# FIT_TCM_ADCLK854.net
KiCad netlist of a schematic drawn in Altium Designer
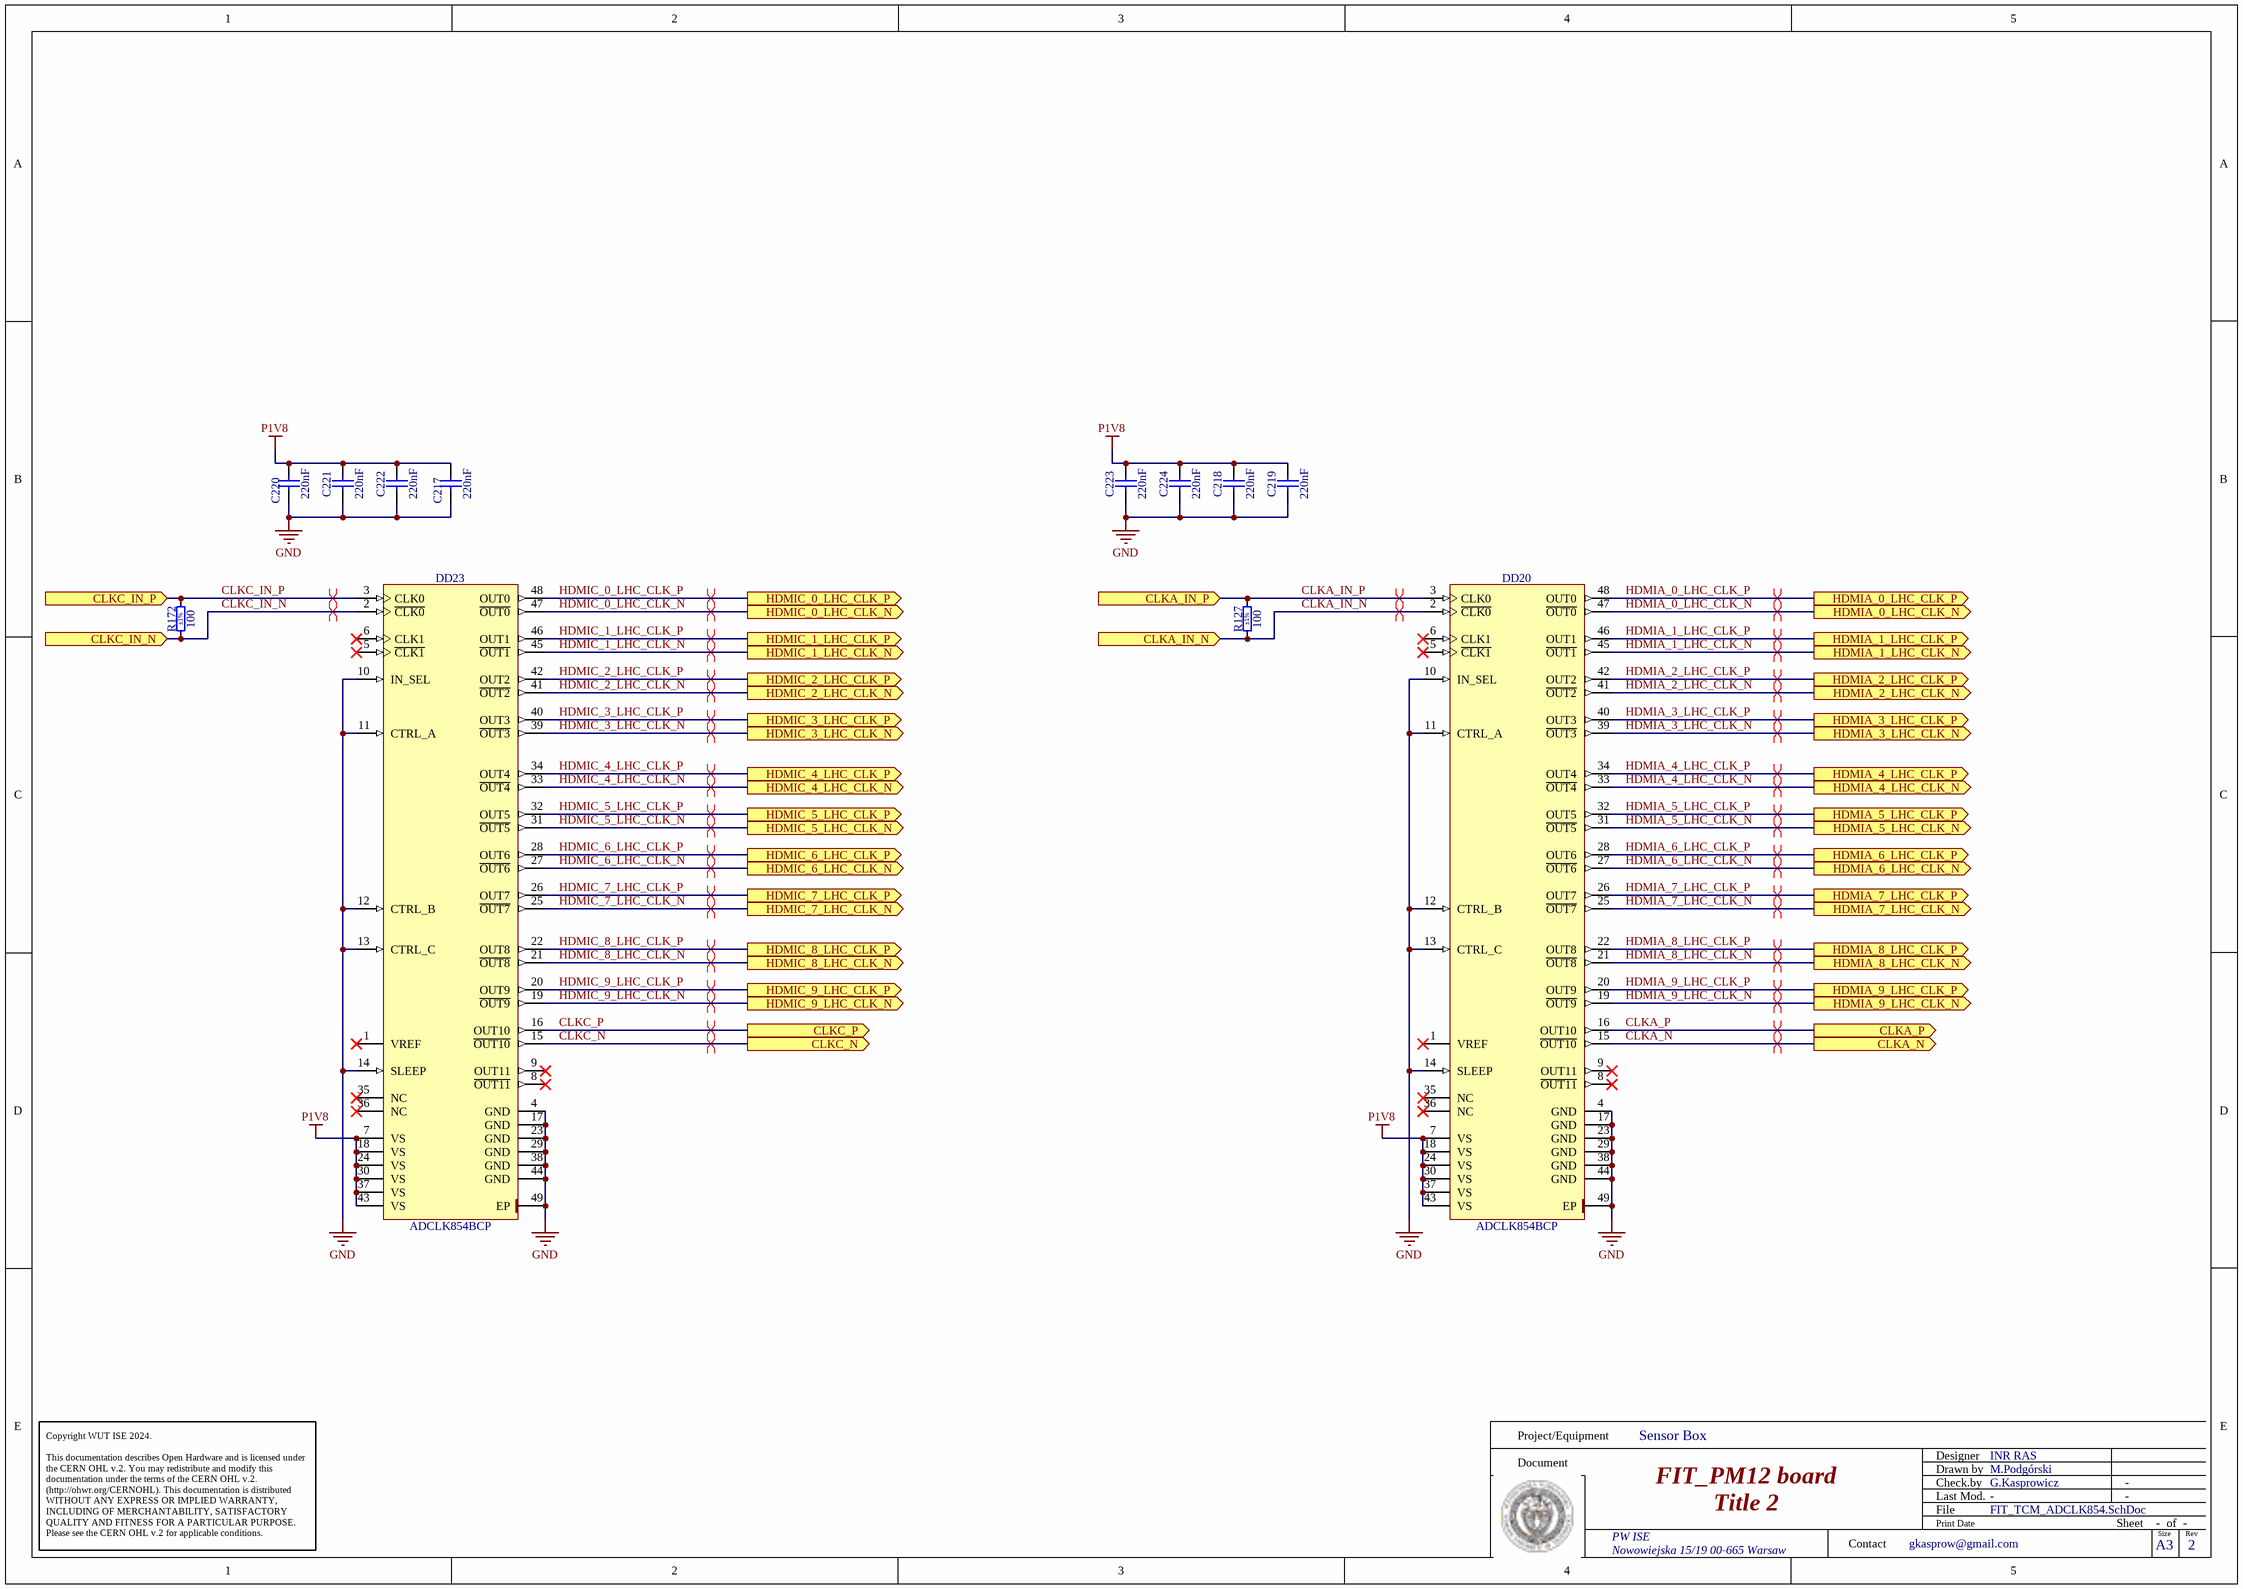
[diagram p0: FIT_TCM_ADCLK854.SchDoc]

(export (version "E")
  (design (tool "Eeschema 10.0.6"))
  (components
    (comp (ref "C217")
      (value "220nF")
      (footprint "CAPC2012X135N")
      (description "Non-polarised capacitor")
      (fields
        (field (name "PART NUMBER") "CC0805_220NF_50V_10%_X7R")
        (field (name "VOLTAGE") "50V")
        (field (name "AUTHOR") "CERN DEM JLC")
      )
      (libsource (lib "Capacitors") (part "Capacitor - non polarized"))
    )
    (comp (ref "C218")
      (value "220nF")
      (footprint "CAPC2012X135N")
      (description "Non-polarised capacitor")
      (fields
        (field (name "PART NUMBER") "CC0805_220NF_50V_10%_X7R")
        (field (name "VOLTAGE") "50V")
        (field (name "AUTHOR") "CERN DEM JLC")
      )
      (libsource (lib "Capacitors") (part "Capacitor - non polarized"))
    )
    (comp (ref "C219")
      (value "220nF")
      (footprint "CAPC2012X135N")
      (description "Non-polarised capacitor")
      (fields
        (field (name "PART NUMBER") "CC0805_220NF_50V_10%_X7R")
        (field (name "VOLTAGE") "50V")
        (field (name "AUTHOR") "CERN DEM JLC")
      )
      (libsource (lib "Capacitors") (part "Capacitor - non polarized"))
    )
    (comp (ref "C220")
      (value "220nF")
      (footprint "CAPC2012X135N")
      (description "Non-polarised capacitor")
      (fields
        (field (name "PART NUMBER") "CC0805_220NF_50V_10%_X7R")
        (field (name "VOLTAGE") "50V")
        (field (name "AUTHOR") "CERN DEM JLC")
      )
      (libsource (lib "Capacitors") (part "Capacitor - non polarized"))
    )
    (comp (ref "C221")
      (value "220nF")
      (footprint "CAPC2012X135N")
      (description "Non-polarised capacitor")
      (fields
        (field (name "PART NUMBER") "CC0805_220NF_50V_10%_X7R")
        (field (name "VOLTAGE") "50V")
        (field (name "AUTHOR") "CERN DEM JLC")
      )
      (libsource (lib "Capacitors") (part "Capacitor - non polarized"))
    )
    (comp (ref "C222")
      (value "220nF")
      (footprint "CAPC2012X135N")
      (description "Non-polarised capacitor")
      (fields
        (field (name "PART NUMBER") "CC0805_220NF_50V_10%_X7R")
        (field (name "VOLTAGE") "50V")
        (field (name "AUTHOR") "CERN DEM JLC")
      )
      (libsource (lib "Capacitors") (part "Capacitor - non polarized"))
    )
    (comp (ref "C223")
      (value "220nF")
      (footprint "CAPC2012X135N")
      (description "Non-polarised capacitor")
      (fields
        (field (name "PART NUMBER") "CC0805_220NF_50V_10%_X7R")
        (field (name "VOLTAGE") "50V")
        (field (name "AUTHOR") "CERN DEM JLC")
      )
      (libsource (lib "Capacitors") (part "Capacitor - non polarized"))
    )
    (comp (ref "C224")
      (value "220nF")
      (footprint "CAPC2012X135N")
      (description "Non-polarised capacitor")
      (fields
        (field (name "PART NUMBER") "CC0805_220NF_50V_10%_X7R")
        (field (name "VOLTAGE") "50V")
        (field (name "AUTHOR") "CERN DEM JLC")
      )
      (libsource (lib "Capacitors") (part "Capacitor - non polarized"))
    )
    (comp (ref "DD20")
      (value "ADCLK854BCP")
      (footprint "QFN50P700X700X80-49N-S290")
      (description "1.8 V, 6 LVDS/12 CMOS Outputs Low Power Clock Fanout Buffer")
      (fields (field (name "MANUFACTURER") "ANALOG DEVICES") (field (name "AUTHOR") "CERN DEM HF"))
      (libsource (lib "ICs And Semiconductors") (part "ADCLK854"))
    )
    (comp (ref "DD23")
      (value "ADCLK854BCP")
      (footprint "QFN50P700X700X80-49N-S290")
      (description "1.8 V, 6 LVDS/12 CMOS Outputs Low Power Clock Fanout Buffer")
      (fields (field (name "MANUFACTURER") "ANALOG DEVICES") (field (name "AUTHOR") "CERN DEM HF"))
      (libsource (lib "ICs And Semiconductors") (part "ADCLK854"))
    )
    (comp (ref "R127")
      (value "100")
      (footprint "RESC1608X55N")
      (description "Resistor - 1%")
      (fields
        (field (name "TOLERANCE") "±1%")
        (field (name "PART NUMBER") "R0603_100R_1%_0.1W_100PPM")
        (field (name "POWER") "0.1W")
        (field (name "AUTHOR") "CERN DEM JLC")
      )
      (libsource (lib "Resistors") (part "Resistor - 1%"))
    )
    (comp (ref "R172")
      (value "100")
      (footprint "RESC1608X55N")
      (description "Resistor - 1%")
      (fields
        (field (name "TOLERANCE") "±1%")
        (field (name "PART NUMBER") "R0603_100R_1%_0.1W_100PPM")
        (field (name "POWER") "0.1W")
        (field (name "AUTHOR") "CERN DEM JLC")
      )
      (libsource (lib "Resistors") (part "Resistor - 1%"))
    )
  )
  (nets
    (net (code "1") (name "/CLKA_IN_N") (class "Default")
      (node (ref "DD20") (pin "2") (pinfunction "~{CLK0}_2") (pintype "input"))
      (node (ref "R127") (pin "1") (pinfunction "1_1") (pintype "passive"))
    )
    (net (code "2") (name "/CLKA_IN_P") (class "Default")
      (node (ref "DD20") (pin "3") (pinfunction "CLK0_3") (pintype "input"))
      (node (ref "R127") (pin "2") (pinfunction "2_2") (pintype "passive"))
    )
    (net (code "3") (name "/CLKA_N") (class "Default")
      (node (ref "DD20") (pin "15") (pinfunction "~{OUT10}_15") (pintype "output"))
    )
    (net (code "4") (name "/CLKA_P") (class "Default")
      (node (ref "DD20") (pin "16") (pinfunction "OUT10_16") (pintype "output"))
    )
    (net (code "5") (name "/CLKC_IN_N") (class "Default")
      (node (ref "DD23") (pin "2") (pinfunction "~{CLK0}_2") (pintype "input"))
      (node (ref "R172") (pin "1") (pinfunction "1_1") (pintype "passive"))
    )
    (net (code "6") (name "/CLKC_IN_P") (class "Default")
      (node (ref "DD23") (pin "3") (pinfunction "CLK0_3") (pintype "input"))
      (node (ref "R172") (pin "2") (pinfunction "2_2") (pintype "passive"))
    )
    (net (code "7") (name "/CLKC_N") (class "Default")
      (node (ref "DD23") (pin "15") (pinfunction "~{OUT10}_15") (pintype "output"))
    )
    (net (code "8") (name "/CLKC_P") (class "Default")
      (node (ref "DD23") (pin "16") (pinfunction "OUT10_16") (pintype "output"))
    )
    (net (code "9") (name "/HDMIA_0_LHC_CLK_N") (class "Default")
      (node (ref "DD20") (pin "47") (pinfunction "~{OUT0}_47") (pintype "output"))
    )
    (net (code "10") (name "/HDMIA_0_LHC_CLK_P") (class "Default")
      (node (ref "DD20") (pin "48") (pinfunction "OUT0_48") (pintype "output"))
    )
    (net (code "11") (name "/HDMIA_1_LHC_CLK_N") (class "Default")
      (node (ref "DD20") (pin "45") (pinfunction "~{OUT1}_45") (pintype "output"))
    )
    (net (code "12") (name "/HDMIA_1_LHC_CLK_P") (class "Default")
      (node (ref "DD20") (pin "46") (pinfunction "OUT1_46") (pintype "output"))
    )
    (net (code "13") (name "/HDMIA_2_LHC_CLK_N") (class "Default")
      (node (ref "DD20") (pin "41") (pinfunction "~{OUT2}_41") (pintype "output"))
    )
    (net (code "14") (name "/HDMIA_2_LHC_CLK_P") (class "Default")
      (node (ref "DD20") (pin "42") (pinfunction "OUT2_42") (pintype "output"))
    )
    (net (code "15") (name "/HDMIA_3_LHC_CLK_N") (class "Default")
      (node (ref "DD20") (pin "39") (pinfunction "~{OUT3}_39") (pintype "output"))
    )
    (net (code "16") (name "/HDMIA_3_LHC_CLK_P") (class "Default")
      (node (ref "DD20") (pin "40") (pinfunction "OUT3_40") (pintype "output"))
    )
    (net (code "17") (name "/HDMIA_4_LHC_CLK_N") (class "Default")
      (node (ref "DD20") (pin "33") (pinfunction "~{OUT4}_33") (pintype "output"))
    )
    (net (code "18") (name "/HDMIA_4_LHC_CLK_P") (class "Default")
      (node (ref "DD20") (pin "34") (pinfunction "OUT4_34") (pintype "output"))
    )
    (net (code "19") (name "/HDMIA_5_LHC_CLK_N") (class "Default")
      (node (ref "DD20") (pin "31") (pinfunction "~{OUT5}_31") (pintype "output"))
    )
    (net (code "20") (name "/HDMIA_5_LHC_CLK_P") (class "Default")
      (node (ref "DD20") (pin "32") (pinfunction "OUT5_32") (pintype "output"))
    )
    (net (code "21") (name "/HDMIA_6_LHC_CLK_N") (class "Default")
      (node (ref "DD20") (pin "27") (pinfunction "~{OUT6}_27") (pintype "output"))
    )
    (net (code "22") (name "/HDMIA_6_LHC_CLK_P") (class "Default")
      (node (ref "DD20") (pin "28") (pinfunction "OUT6_28") (pintype "output"))
    )
    (net (code "23") (name "/HDMIA_7_LHC_CLK_N") (class "Default")
      (node (ref "DD20") (pin "25") (pinfunction "~{OUT7}_25") (pintype "output"))
    )
    (net (code "24") (name "/HDMIA_7_LHC_CLK_P") (class "Default")
      (node (ref "DD20") (pin "26") (pinfunction "OUT7_26") (pintype "output"))
    )
    (net (code "25") (name "/HDMIA_8_LHC_CLK_N") (class "Default")
      (node (ref "DD20") (pin "21") (pinfunction "~{OUT8}_21") (pintype "output"))
    )
    (net (code "26") (name "/HDMIA_8_LHC_CLK_P") (class "Default")
      (node (ref "DD20") (pin "22") (pinfunction "OUT8_22") (pintype "output"))
    )
    (net (code "27") (name "/HDMIA_9_LHC_CLK_N") (class "Default")
      (node (ref "DD20") (pin "19") (pinfunction "~{OUT9}_19") (pintype "output"))
    )
    (net (code "28") (name "/HDMIA_9_LHC_CLK_P") (class "Default")
      (node (ref "DD20") (pin "20") (pinfunction "OUT9_20") (pintype "output"))
    )
    (net (code "29") (name "/HDMIC_0_LHC_CLK_N") (class "Default")
      (node (ref "DD23") (pin "47") (pinfunction "~{OUT0}_47") (pintype "output"))
    )
    (net (code "30") (name "/HDMIC_0_LHC_CLK_P") (class "Default")
      (node (ref "DD23") (pin "48") (pinfunction "OUT0_48") (pintype "output"))
    )
    (net (code "31") (name "/HDMIC_1_LHC_CLK_N") (class "Default")
      (node (ref "DD23") (pin "45") (pinfunction "~{OUT1}_45") (pintype "output"))
    )
    (net (code "32") (name "/HDMIC_1_LHC_CLK_P") (class "Default")
      (node (ref "DD23") (pin "46") (pinfunction "OUT1_46") (pintype "output"))
    )
    (net (code "33") (name "/HDMIC_2_LHC_CLK_N") (class "Default")
      (node (ref "DD23") (pin "41") (pinfunction "~{OUT2}_41") (pintype "output"))
    )
    (net (code "34") (name "/HDMIC_2_LHC_CLK_P") (class "Default")
      (node (ref "DD23") (pin "42") (pinfunction "OUT2_42") (pintype "output"))
    )
    (net (code "35") (name "/HDMIC_3_LHC_CLK_N") (class "Default")
      (node (ref "DD23") (pin "39") (pinfunction "~{OUT3}_39") (pintype "output"))
    )
    (net (code "36") (name "/HDMIC_3_LHC_CLK_P") (class "Default")
      (node (ref "DD23") (pin "40") (pinfunction "OUT3_40") (pintype "output"))
    )
    (net (code "37") (name "/HDMIC_4_LHC_CLK_N") (class "Default")
      (node (ref "DD23") (pin "33") (pinfunction "~{OUT4}_33") (pintype "output"))
    )
    (net (code "38") (name "/HDMIC_4_LHC_CLK_P") (class "Default")
      (node (ref "DD23") (pin "34") (pinfunction "OUT4_34") (pintype "output"))
    )
    (net (code "39") (name "/HDMIC_5_LHC_CLK_N") (class "Default")
      (node (ref "DD23") (pin "31") (pinfunction "~{OUT5}_31") (pintype "output"))
    )
    (net (code "40") (name "/HDMIC_5_LHC_CLK_P") (class "Default")
      (node (ref "DD23") (pin "32") (pinfunction "OUT5_32") (pintype "output"))
    )
    (net (code "41") (name "/HDMIC_6_LHC_CLK_N") (class "Default")
      (node (ref "DD23") (pin "27") (pinfunction "~{OUT6}_27") (pintype "output"))
    )
    (net (code "42") (name "/HDMIC_6_LHC_CLK_P") (class "Default")
      (node (ref "DD23") (pin "28") (pinfunction "OUT6_28") (pintype "output"))
    )
    (net (code "43") (name "/HDMIC_7_LHC_CLK_N") (class "Default")
      (node (ref "DD23") (pin "25") (pinfunction "~{OUT7}_25") (pintype "output"))
    )
    (net (code "44") (name "/HDMIC_7_LHC_CLK_P") (class "Default")
      (node (ref "DD23") (pin "26") (pinfunction "OUT7_26") (pintype "output"))
    )
    (net (code "45") (name "/HDMIC_8_LHC_CLK_N") (class "Default")
      (node (ref "DD23") (pin "21") (pinfunction "~{OUT8}_21") (pintype "output"))
    )
    (net (code "46") (name "/HDMIC_8_LHC_CLK_P") (class "Default")
      (node (ref "DD23") (pin "22") (pinfunction "OUT8_22") (pintype "output"))
    )
    (net (code "47") (name "/HDMIC_9_LHC_CLK_N") (class "Default")
      (node (ref "DD23") (pin "19") (pinfunction "~{OUT9}_19") (pintype "output"))
    )
    (net (code "48") (name "/HDMIC_9_LHC_CLK_P") (class "Default")
      (node (ref "DD23") (pin "20") (pinfunction "OUT9_20") (pintype "output"))
    )
    (net (code "49") (name "GND") (class "Default")
      (node (ref "C217") (pin "1") (pinfunction "1_1") (pintype "passive"))
      (node (ref "C218") (pin "1") (pinfunction "1_1") (pintype "passive"))
      (node (ref "C219") (pin "1") (pinfunction "1_1") (pintype "passive"))
      (node (ref "C220") (pin "1") (pinfunction "1_1") (pintype "passive"))
      (node (ref "C221") (pin "1") (pinfunction "1_1") (pintype "passive"))
      (node (ref "C222") (pin "1") (pinfunction "1_1") (pintype "passive"))
      (node (ref "C223") (pin "1") (pinfunction "1_1") (pintype "passive"))
      (node (ref "C224") (pin "1") (pinfunction "1_1") (pintype "passive"))
      (node (ref "DD20") (pin "10") (pinfunction "IN_SEL_10") (pintype "input"))
      (node (ref "DD20") (pin "11") (pinfunction "CTRL_A_11") (pintype "input"))
      (node (ref "DD20") (pin "12") (pinfunction "CTRL_B_12") (pintype "input"))
      (node (ref "DD20") (pin "13") (pinfunction "CTRL_C_13") (pintype "input"))
      (node (ref "DD20") (pin "14") (pinfunction "SLEEP_14") (pintype "input"))
      (node (ref "DD20") (pin "17") (pinfunction "GND_17") (pintype "power_in"))
      (node (ref "DD20") (pin "23") (pinfunction "GND_23") (pintype "power_in"))
      (node (ref "DD20") (pin "29") (pinfunction "GND_29") (pintype "power_in"))
      (node (ref "DD20") (pin "38") (pinfunction "GND_38") (pintype "power_in"))
      (node (ref "DD20") (pin "4") (pinfunction "GND_4") (pintype "power_in"))
      (node (ref "DD20") (pin "44") (pinfunction "GND_44") (pintype "power_in"))
      (node (ref "DD20") (pin "49") (pinfunction "EP_49") (pintype "power_in"))
      (node (ref "DD23") (pin "10") (pinfunction "IN_SEL_10") (pintype "input"))
      (node (ref "DD23") (pin "11") (pinfunction "CTRL_A_11") (pintype "input"))
      (node (ref "DD23") (pin "12") (pinfunction "CTRL_B_12") (pintype "input"))
      (node (ref "DD23") (pin "13") (pinfunction "CTRL_C_13") (pintype "input"))
      (node (ref "DD23") (pin "14") (pinfunction "SLEEP_14") (pintype "input"))
      (node (ref "DD23") (pin "17") (pinfunction "GND_17") (pintype "power_in"))
      (node (ref "DD23") (pin "23") (pinfunction "GND_23") (pintype "power_in"))
      (node (ref "DD23") (pin "29") (pinfunction "GND_29") (pintype "power_in"))
      (node (ref "DD23") (pin "38") (pinfunction "GND_38") (pintype "power_in"))
      (node (ref "DD23") (pin "4") (pinfunction "GND_4") (pintype "power_in"))
      (node (ref "DD23") (pin "44") (pinfunction "GND_44") (pintype "power_in"))
      (node (ref "DD23") (pin "49") (pinfunction "EP_49") (pintype "power_in"))
    )
    (net (code "50") (name "P1V8") (class "Default")
      (node (ref "C217") (pin "2") (pinfunction "2_2") (pintype "passive"))
      (node (ref "C218") (pin "2") (pinfunction "2_2") (pintype "passive"))
      (node (ref "C219") (pin "2") (pinfunction "2_2") (pintype "passive"))
      (node (ref "C220") (pin "2") (pinfunction "2_2") (pintype "passive"))
      (node (ref "C221") (pin "2") (pinfunction "2_2") (pintype "passive"))
      (node (ref "C222") (pin "2") (pinfunction "2_2") (pintype "passive"))
      (node (ref "C223") (pin "2") (pinfunction "2_2") (pintype "passive"))
      (node (ref "C224") (pin "2") (pinfunction "2_2") (pintype "passive"))
      (node (ref "DD20") (pin "18") (pinfunction "VS_18") (pintype "power_in"))
      (node (ref "DD20") (pin "24") (pinfunction "VS_24") (pintype "power_in"))
      (node (ref "DD20") (pin "30") (pinfunction "VS_30") (pintype "power_in"))
      (node (ref "DD20") (pin "37") (pinfunction "VS_37") (pintype "power_in"))
      (node (ref "DD20") (pin "43") (pinfunction "VS_43") (pintype "power_in"))
      (node (ref "DD20") (pin "7") (pinfunction "VS_7") (pintype "power_in"))
      (node (ref "DD23") (pin "18") (pinfunction "VS_18") (pintype "power_in"))
      (node (ref "DD23") (pin "24") (pinfunction "VS_24") (pintype "power_in"))
      (node (ref "DD23") (pin "30") (pinfunction "VS_30") (pintype "power_in"))
      (node (ref "DD23") (pin "37") (pinfunction "VS_37") (pintype "power_in"))
      (node (ref "DD23") (pin "43") (pinfunction "VS_43") (pintype "power_in"))
      (node (ref "DD23") (pin "7") (pinfunction "VS_7") (pintype "power_in"))
    )
    (net (code "51") (name "unconnected-(DD20-CLK1-Pad6)") (class "Default")
      (node (ref "DD20") (pin "6") (pinfunction "CLK1_6") (pintype "input+no_connect"))
    )
    (net (code "52") (name "unconnected-(DD20-NC-Pad35)") (class "Default")
      (node (ref "DD20") (pin "35") (pinfunction "NC_35") (pintype "power_in+no_connect"))
    )
    (net (code "53") (name "unconnected-(DD20-NC-Pad36)") (class "Default")
      (node (ref "DD20") (pin "36") (pinfunction "NC_36") (pintype "power_in+no_connect"))
    )
    (net (code "54") (name "unconnected-(DD20-OUT11-Pad9)") (class "Default")
      (node (ref "DD20") (pin "9") (pinfunction "OUT11_9") (pintype "output+no_connect"))
    )
    (net (code "55") (name "unconnected-(DD20-VREF-Pad1)") (class "Default")
      (node (ref "DD20") (pin "1") (pinfunction "VREF_1") (pintype "power_in+no_connect"))
    )
    (net (code "56") (name "unconnected-(DD20-~{CLK1}-Pad5)") (class "Default")
      (node (ref "DD20") (pin "5") (pinfunction "~{CLK1}_5") (pintype "input+no_connect"))
    )
    (net (code "57") (name "unconnected-(DD20-~{OUT11}-Pad8)") (class "Default")
      (node (ref "DD20") (pin "8") (pinfunction "~{OUT11}_8") (pintype "output+no_connect"))
    )
    (net (code "58") (name "unconnected-(DD23-CLK1-Pad6)") (class "Default")
      (node (ref "DD23") (pin "6") (pinfunction "CLK1_6") (pintype "input+no_connect"))
    )
    (net (code "59") (name "unconnected-(DD23-NC-Pad35)") (class "Default")
      (node (ref "DD23") (pin "35") (pinfunction "NC_35") (pintype "power_in+no_connect"))
    )
    (net (code "60") (name "unconnected-(DD23-NC-Pad36)") (class "Default")
      (node (ref "DD23") (pin "36") (pinfunction "NC_36") (pintype "power_in+no_connect"))
    )
    (net (code "61") (name "unconnected-(DD23-OUT11-Pad9)") (class "Default")
      (node (ref "DD23") (pin "9") (pinfunction "OUT11_9") (pintype "output+no_connect"))
    )
    (net (code "62") (name "unconnected-(DD23-VREF-Pad1)") (class "Default")
      (node (ref "DD23") (pin "1") (pinfunction "VREF_1") (pintype "power_in+no_connect"))
    )
    (net (code "63") (name "unconnected-(DD23-~{CLK1}-Pad5)") (class "Default")
      (node (ref "DD23") (pin "5") (pinfunction "~{CLK1}_5") (pintype "input+no_connect"))
    )
    (net (code "64") (name "unconnected-(DD23-~{OUT11}-Pad8)") (class "Default")
      (node (ref "DD23") (pin "8") (pinfunction "~{OUT11}_8") (pintype "output+no_connect"))
    )
  )
)
